# Summits7_Sch.net
KiCad netlist of a schematic drawn in Altium Designer
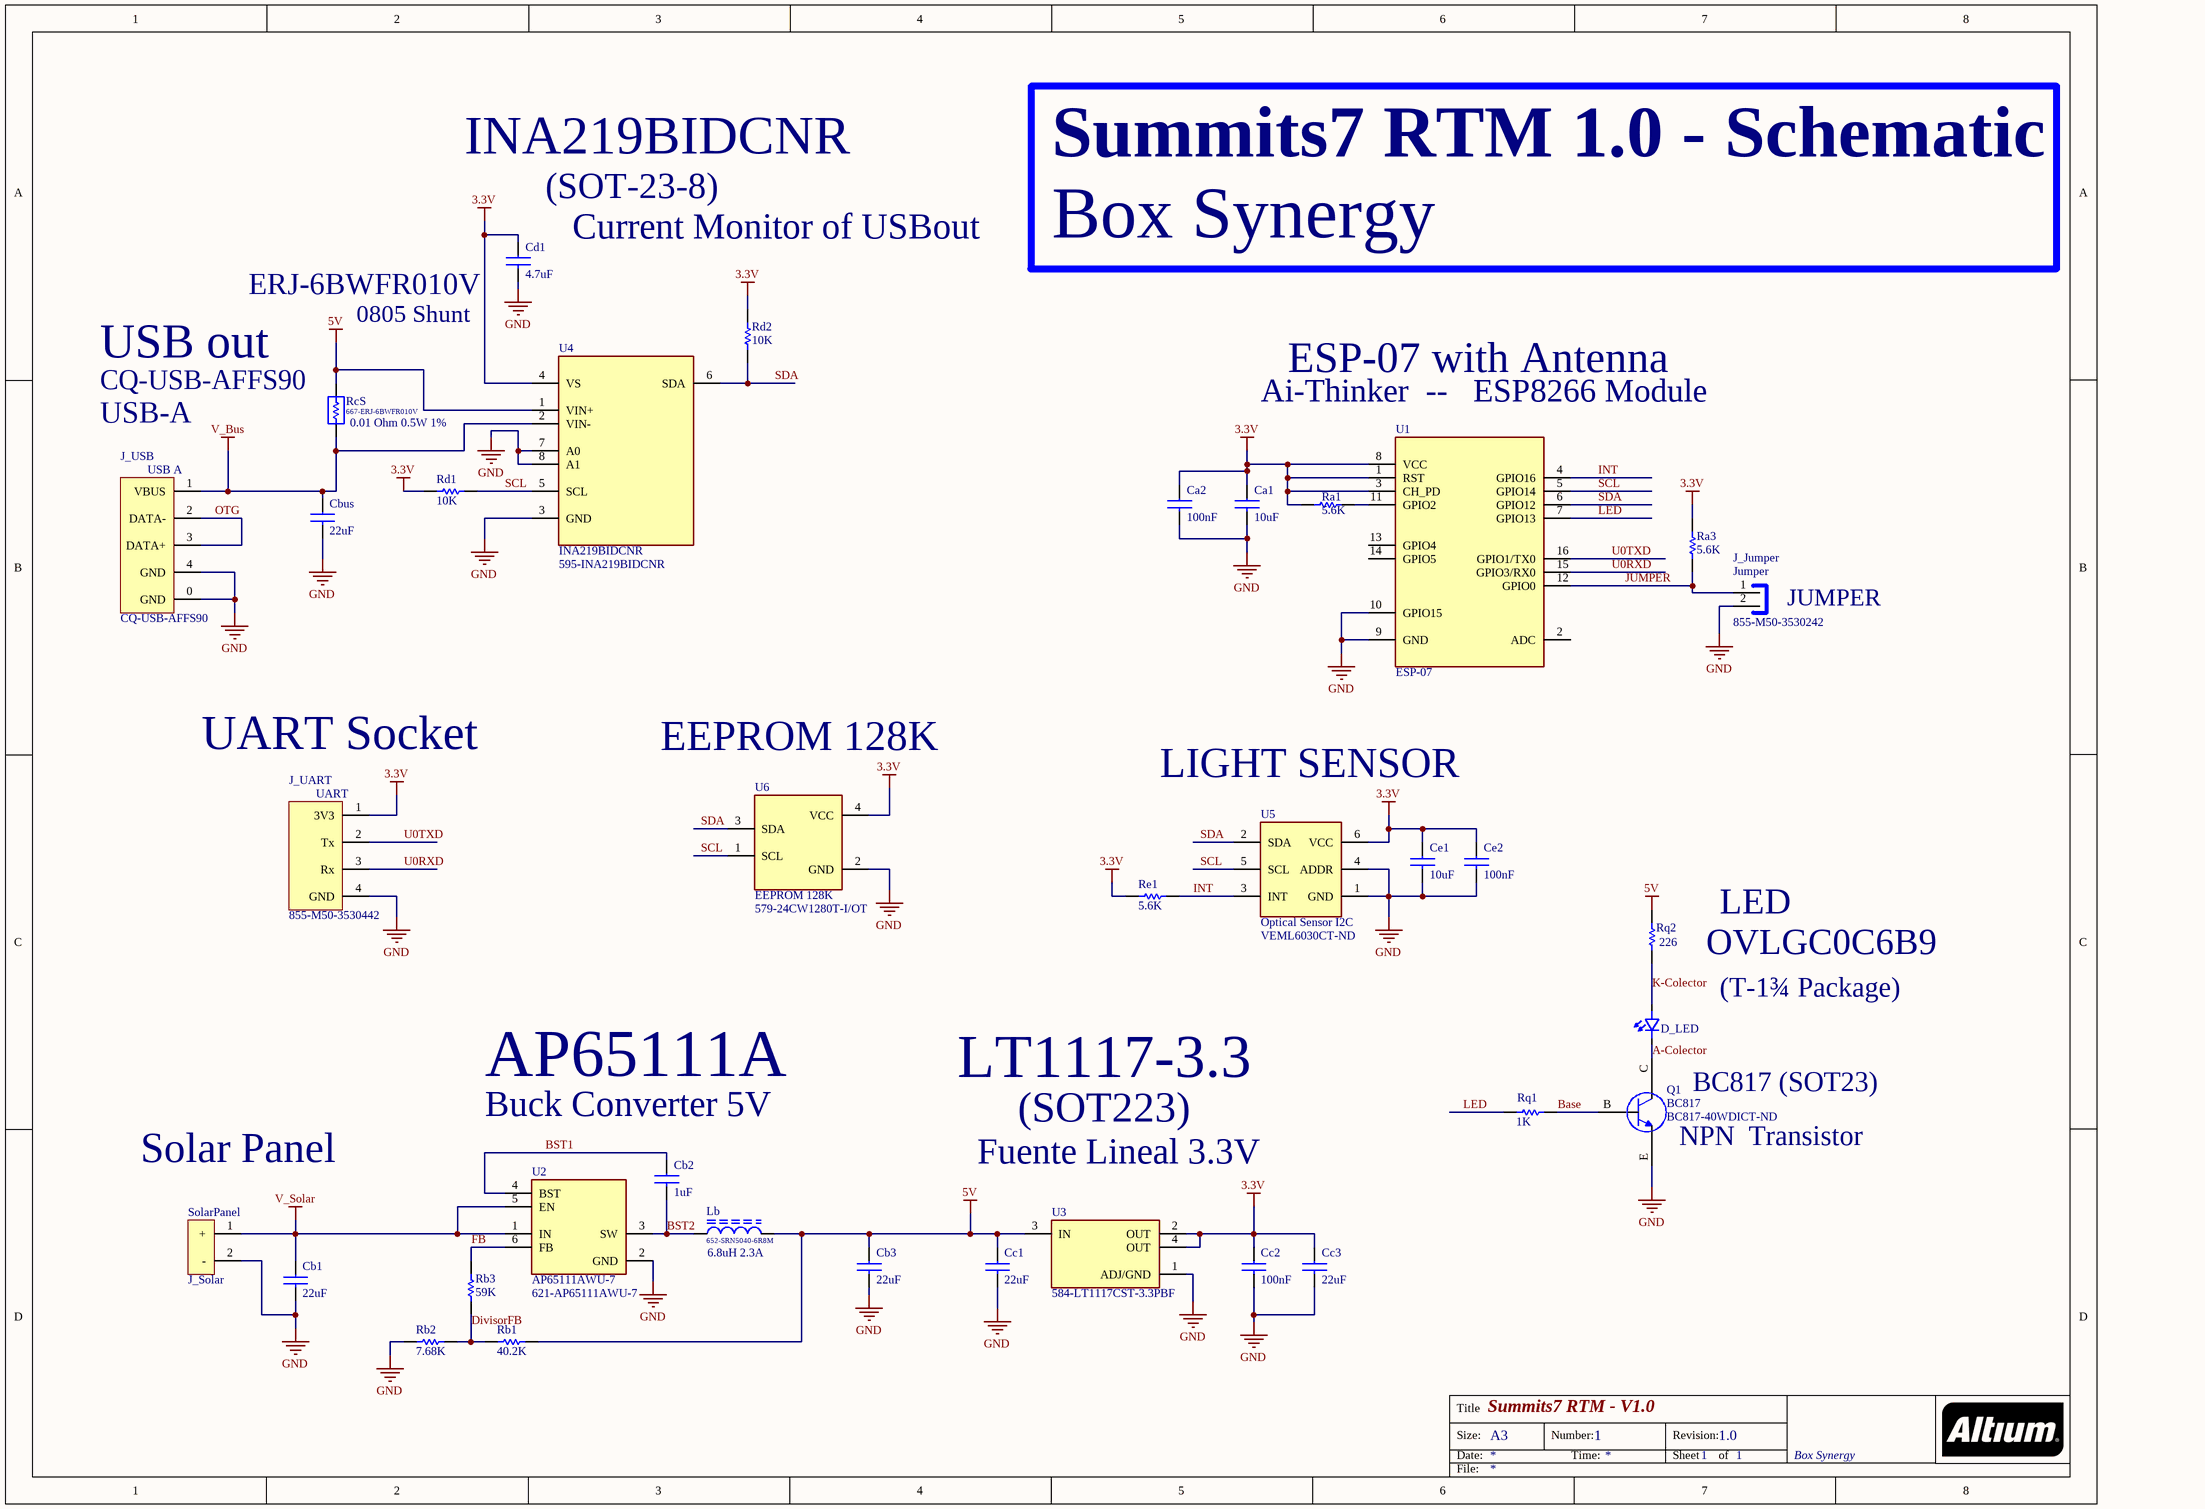
[diagram p0: Summits7_Sch.SchDoc]

(export (version "E")
  (design (tool "Eeschema 10.0.6"))
  (components
    (comp (ref "Ca1")
      (value "10uF")
      (footprint "CAP_0603")
      (description "Capac Ceramic SMD")
      (libsource (lib "Summits7Beta_LIB_Pasivos_Sch") (part "Cap_0603_Ceramic"))
    )
    (comp (ref "Ca2")
      (value "100nF")
      (footprint "CAP_0603")
      (description "Capac Ceramic SMD")
      (libsource (lib "Summits7Beta_LIB_Pasivos_Sch") (part "Cap_0603_Ceramic"))
    )
    (comp (ref "Cb1")
      (value "22uF")
      (footprint "CAP_1210")
      (description "Capac Ceramic SMD")
      (libsource (lib "Summits7Beta_LIB_Pasivos_Sch") (part "Cap_1210_Ceramic"))
    )
    (comp (ref "Cb2")
      (value "1uF")
      (footprint "CAP_0603")
      (description "Capac Ceramic SMD")
      (libsource (lib "Summits7Beta_LIB_Pasivos_Sch") (part "Cap_0603_Ceramic"))
    )
    (comp (ref "Cb3")
      (value "22uF")
      (footprint "CAP_1210")
      (description "Capac Ceramic SMD")
      (libsource (lib "Summits7Beta_LIB_Pasivos_Sch") (part "Cap_1210_Ceramic"))
    )
    (comp (ref "Cbus")
      (value "22uF")
      (footprint "CAP_1210")
      (description "Capac Ceramic SMD")
      (libsource (lib "Summits7Beta_LIB_Pasivos_Sch") (part "Cap_1210_Ceramic"))
    )
    (comp (ref "Cc1")
      (value "22uF")
      (footprint "CAP_0603")
      (description "Capac Ceramic SMD")
      (libsource (lib "Summits7Beta_LIB_Pasivos_Sch") (part "Cap_0603_Ceramic"))
    )
    (comp (ref "Cc2")
      (value "100nF")
      (footprint "CAP_0603")
      (description "Capac Ceramic SMD")
      (libsource (lib "Summits7Beta_LIB_Pasivos_Sch") (part "Cap_0603_Ceramic"))
    )
    (comp (ref "Cc3")
      (value "22uF")
      (footprint "CAP_1210")
      (description "Capac Ceramic SMD")
      (libsource (lib "Summits7Beta_LIB_Pasivos_Sch") (part "Cap_1210_Ceramic"))
    )
    (comp (ref "Cd1")
      (value "4.7uF")
      (footprint "CAP_0603")
      (description "Capac Ceramic SMD")
      (libsource (lib "Summits7Beta_LIB_Pasivos_Sch") (part "Cap_0603_Ceramic"))
    )
    (comp (ref "Ce1")
      (value "10uF")
      (footprint "CAP_0603")
      (description "Capac Ceramic SMD")
      (libsource (lib "Summits7Beta_LIB_Pasivos_Sch") (part "Cap_0603_Ceramic"))
    )
    (comp (ref "Ce2")
      (value "100nF")
      (footprint "CAP_0603")
      (description "Capac Ceramic SMD")
      (libsource (lib "Summits7Beta_LIB_Pasivos_Sch") (part "Cap_0603_Ceramic"))
    )
    (comp (ref "D_LED")
      (value "OVLGC0C6B9")
      (footprint "LED")
      (description "LED Green-Blue 505nm")
      (fields (field (name "MF") "Broadcom Limited") (field (name "MP") "HSMW-C191"))
      (libsource (lib "Summits7Beta_LIB_Otros_Sch") (part "OVLGC0C6B9"))
    )
    (comp (ref "J_Jumper")
      (value "M50-3530242")
      (footprint "JUMPER-1.27 mm")
      (description "1.27mm Pin Header 2x1")
      (fields (field (name "SUPPLIER PART NUMBER 1") "855-M50-3530242"))
      (libsource (lib "Summits7Beta_LIB_Conectores_Sch") (part "Jumper"))
    )
    (comp (ref "J_Solar")
      (value "Connx2_Panel")
      (footprint "PANEL_IN")
      (description "Conector del Panel")
      (libsource (lib "Summits7Beta_LIB_Conectores_Sch") (part "Connx2_Panel"))
    )
    (comp (ref "J_UART")
      (value "M50-3530442")
      (footprint "UART-1.27mm")
      (description "1.27mm Pin Header 4x1")
      (fields (field (name "SUPPLIER PART NUMBER 1") "855-M50-3530442"))
      (libsource (lib "Summits7Beta_LIB_Conectores_Sch") (part "Connx4_UART"))
    )
    (comp (ref "J_USB")
      (value "CQ-USB-AFFS90")
      (footprint "USB-A__IPX8")
      (description "Conector del USB   --   CQ-USB-AFFS90")
      (libsource (lib "Summits7Beta_LIB_Conectores_Sch") (part "USB-A 5V"))
    )
    (comp (ref "Lb")
      (value "6.8uH 2.3A")
      (footprint "Inductor_SRN5040")
      (description "Inductor_SRN5040")
      (fields (field (name "MF") "Vishay Dale") (field (name "SUPPLIER PART NUMBER 1") "652-SRN5040-6R8M"))
      (libsource (lib "Summits7Beta_LIB_Pasivos_Sch") (part "Ind_SRN5040"))
    )
    (comp (ref "Q1")
      (value "BC817")
      (footprint "Transistor_SOT23-3")
      (description "Transistor NPN. Leave 2.5mm height from PCB")
      (fields (field (name "SUPPLIER PART NUMBER 1") "BC817-40WDICT-ND"))
      (libsource (lib "Summits7Beta_LIB_Integrados_Sch") (part "BC817"))
    )
    (comp (ref "Ra1")
      (value "5.6K")
      (footprint "RES_0603")
      (description "Resistor SMD")
      (fields (field (name "PUBLISHER") "Altium Limited"))
      (libsource (lib "Summits7Beta_LIB_Pasivos_Sch") (part "Res_0603"))
    )
    (comp (ref "Ra3")
      (value "5.6K")
      (footprint "RES_0603")
      (description "Resistor SMD")
      (fields (field (name "PUBLISHER") "Altium Limited"))
      (libsource (lib "Summits7Beta_LIB_Pasivos_Sch") (part "Res_0603"))
    )
    (comp (ref "Rb1")
      (value "40.2K")
      (footprint "RES_0603")
      (description "Resistor SMD")
      (fields (field (name "PUBLISHER") "Altium Limited"))
      (libsource (lib "Summits7Beta_LIB_Pasivos_Sch") (part "Res_0603"))
    )
    (comp (ref "Rb2")
      (value "7.68K")
      (footprint "RES_0603")
      (description "Resistor SMD")
      (fields (field (name "PUBLISHER") "Altium Limited"))
      (libsource (lib "Summits7Beta_LIB_Pasivos_Sch") (part "Res_0603"))
    )
    (comp (ref "Rb3")
      (value "59K")
      (footprint "RES_0603")
      (description "Resistor SMD")
      (fields (field (name "PUBLISHER") "Altium Limited"))
      (libsource (lib "Summits7Beta_LIB_Pasivos_Sch") (part "Res_0603"))
    )
    (comp (ref "RcS")
      (value "0.01 Ohm 0.5W 1%")
      (footprint "RES-SHUNT-0805")
      (description "Shunt")
      (fields
        (field (name "SUPPLIER PART NUMBER 1") "667-ERJ-6BWFR010V")
        (field (name "PUBLISHER") "Altium Limited")
      )
      (libsource (lib "Summits7Beta_LIB_Pasivos_Sch") (part "Shunt_0805"))
    )
    (comp (ref "Rd1")
      (value "10K")
      (footprint "RES_0603")
      (description "Resistor SMD")
      (fields (field (name "PUBLISHER") "Altium Limited"))
      (libsource (lib "Summits7Beta_LIB_Pasivos_Sch") (part "Res_0603"))
    )
    (comp (ref "Rd2")
      (value "10K")
      (footprint "RES_0603")
      (description "Resistor SMD")
      (fields (field (name "PUBLISHER") "Altium Limited"))
      (libsource (lib "Summits7Beta_LIB_Pasivos_Sch") (part "Res_0603"))
    )
    (comp (ref "Re1")
      (value "5.6K")
      (footprint "RES_0603")
      (description "Resistor SMD")
      (fields (field (name "PUBLISHER") "Altium Limited"))
      (libsource (lib "Summits7Beta_LIB_Pasivos_Sch") (part "Res_0603"))
    )
    (comp (ref "Rq1")
      (value "1K")
      (footprint "RES_0603")
      (description "Resistor SMD")
      (fields (field (name "PUBLISHER") "Altium Limited"))
      (libsource (lib "Summits7Beta_LIB_Pasivos_Sch") (part "Res_0603"))
    )
    (comp (ref "Rq2")
      (value "226")
      (footprint "RES_0603")
      (description "Resistor SMD")
      (fields (field (name "PUBLISHER") "Altium Limited"))
      (libsource (lib "Summits7Beta_LIB_Pasivos_Sch") (part "Res_0603"))
    )
    (comp (ref "U1")
      (value "ESP-07")
      (footprint "ESP-07")
      (description "ESP07 Module with Antenna Ai-Thinker")
      (fields (field (name "MP") "AP65111AWU-7") (field (name "MF") "Diodes Inc."))
      (libsource (lib "Summits7Beta_LIB_Integrados_Sch") (part "ESP-07"))
    )
    (comp (ref "U2")
      (value "AP65111AWU-7")
      (footprint "AP65111A-SOT23-6")
      (description "Buck Switching Regulator IC Positive Adjustable 0.8V 1 Output 1.5A SOT-23-6 Thin, TSOT-23-6")
      (fields (field (name "MF") "Diodes Inc.") (field (name "SUPPLIER PART NUMBER 1") "621-AP65111AWU-7"))
      (libsource (lib "Summits7Beta_LIB_Integrados_Sch") (part "AP65111AWU-7"))
    )
    (comp (ref "U3")
      (value "LT1117IST-3.3")
      (footprint "LT1117IST-3.3_SOT-223")
      (description "LDO Regulator Pos 3.3V 0.8A Automotive 4-Pin_3+Tab_ SOT-223 Tube")
      (fields
        (field (name "MP") "LT1117IST-5#PBF")
        (field (name "MF") "Analog Devices")
        (field (name "SUPPLIER PART NUMBER 1") "584-LT1117CST-3.3PBF")
      )
      (libsource (lib "Summits7Beta_LIB_Integrados_Sch") (part "LT1117IST-3.3"))
    )
    (comp (ref "U4")
      (value "INA219BIDCNR")
      (footprint "INA219B SOT23")
      (description "Current Monitor Regulator High-Side 10mA SOT-23-8")
      (fields
        (field (name "DIGI-KEY_PART_NUMBER") "296-46420-1-ND")
        (field (name "MF") "Texas Instruments")
        (field (name "SUPPLIER PART NUMBER 1") "595-INA219BIDCNR")
      )
      (libsource (lib "Summits7Beta_LIB_Integrados_Sch") (part "INA219BIDCNR"))
    )
    (comp (ref "U5")
      (value "Optical Sensor I2C")
      (footprint "VEML6030")
      (description "Optical Ambiental Light Sensor I2C with Interrupt")
      (fields (field (name "SUPPLIER PART NUMBER 1") "VEML6030CT-ND"))
      (libsource (lib "Summits7Beta_LIB_Integrados_Sch") (part "VEML6030"))
    )
    (comp (ref "U6")
      (value "EEPROM 128K")
      (footprint "24CW128")
      (fields (field (name "SUPPLIER PART NUMBER 1") "579-24CW1280T-I/OT"))
      (libsource (lib "Summits7Beta_LIB_Integrados_Sch") (part "24CW1280T-I/OT"))
    )
  )
  (nets
    (net (code "1") (name "/A-Colector") (class "Default")
      (node (ref "D_LED") (pin "1") (pinfunction "K_1") (pintype "passive"))
      (node (ref "Q1") (pin "C") (pinfunction "C_C") (pintype "passive"))
    )
    (net (code "2") (name "/BST1") (class "Default")
      (node (ref "Cb2") (pin "1") (pinfunction "1_1") (pintype "passive"))
      (node (ref "U2") (pin "4") (pinfunction "BST_4") (pintype "passive"))
    )
    (net (code "3") (name "/BST2") (class "Default")
      (node (ref "Cb2") (pin "2") (pinfunction "2_2") (pintype "passive"))
      (node (ref "Lb") (pin "2") (pinfunction "2_2") (pintype "passive"))
      (node (ref "U2") (pin "3") (pinfunction "SW_3") (pintype "passive"))
    )
    (net (code "4") (name "/Base") (class "Default")
      (node (ref "Q1") (pin "B") (pinfunction "B_B") (pintype "passive"))
      (node (ref "Rq1") (pin "1") (pinfunction "1_1") (pintype "passive"))
    )
    (net (code "5") (name "/DivisorFB") (class "Default")
      (node (ref "Rb1") (pin "2") (pinfunction "2_2") (pintype "passive"))
      (node (ref "Rb2") (pin "1") (pinfunction "1_1") (pintype "passive"))
      (node (ref "Rb3") (pin "2") (pinfunction "2_2") (pintype "passive"))
    )
    (net (code "6") (name "/FB") (class "Default")
      (node (ref "Rb3") (pin "1") (pinfunction "1_1") (pintype "passive"))
      (node (ref "U2") (pin "6") (pinfunction "FB_6") (pintype "passive"))
    )
    (net (code "7") (name "/INT") (class "Default")
      (node (ref "Re1") (pin "2") (pinfunction "2_2") (pintype "passive"))
      (node (ref "U1") (pin "4") (pinfunction "GPIO16_4") (pintype "passive"))
      (node (ref "U5") (pin "3") (pinfunction "INT_3") (pintype "passive"))
    )
    (net (code "8") (name "/JUMPER") (class "Default")
      (node (ref "J_Jumper") (pin "1") (pinfunction "1_1") (pintype "passive"))
      (node (ref "Ra3") (pin "2") (pinfunction "2_2") (pintype "passive"))
      (node (ref "U1") (pin "12") (pinfunction "GPIO0_12") (pintype "passive"))
    )
    (net (code "9") (name "/K-Colector") (class "Default")
      (node (ref "D_LED") (pin "2") (pinfunction "A_2") (pintype "passive"))
      (node (ref "Rq2") (pin "2") (pinfunction "2_2") (pintype "passive"))
    )
    (net (code "10") (name "/LED") (class "Default")
      (node (ref "Rq1") (pin "2") (pinfunction "2_2") (pintype "passive"))
      (node (ref "U1") (pin "7") (pinfunction "GPIO13_7") (pintype "passive"))
    )
    (net (code "11") (name "/OTG") (class "Default")
      (node (ref "J_USB") (pin "2") (pinfunction "DATA-_2") (pintype "passive"))
      (node (ref "J_USB") (pin "3") (pinfunction "DATA+_3") (pintype "passive"))
    )
    (net (code "12") (name "/SCL") (class "Default")
      (node (ref "Rd1") (pin "2") (pinfunction "2_2") (pintype "passive"))
      (node (ref "U1") (pin "5") (pinfunction "GPIO14_5") (pintype "passive"))
      (node (ref "U4") (pin "5") (pinfunction "SCL_5") (pintype "passive"))
      (node (ref "U5") (pin "5") (pinfunction "SCL_5") (pintype "passive"))
      (node (ref "U6") (pin "1") (pinfunction "SCL_1") (pintype "passive"))
    )
    (net (code "13") (name "/SDA") (class "Default")
      (node (ref "Rd2") (pin "2") (pinfunction "2_2") (pintype "passive"))
      (node (ref "U1") (pin "6") (pinfunction "GPIO12_6") (pintype "passive"))
      (node (ref "U4") (pin "6") (pinfunction "SDA_6") (pintype "passive"))
      (node (ref "U5") (pin "2") (pinfunction "SDA_2") (pintype "passive"))
      (node (ref "U6") (pin "3") (pinfunction "SDA_3") (pintype "passive"))
    )
    (net (code "14") (name "/U0RXD") (class "Default")
      (node (ref "J_UART") (pin "3") (pinfunction "Rx_3") (pintype "passive"))
      (node (ref "U1") (pin "15") (pinfunction "GPIO3/RX0_15") (pintype "passive"))
    )
    (net (code "15") (name "/U0TXD") (class "Default")
      (node (ref "J_UART") (pin "2") (pinfunction "Tx_2") (pintype "passive"))
      (node (ref "U1") (pin "16") (pinfunction "GPIO1/TX0_16") (pintype "passive"))
    )
    (net (code "16") (name "3.3V") (class "Default")
      (node (ref "Ca1") (pin "1") (pinfunction "1_1") (pintype "passive"))
      (node (ref "Ca2") (pin "1") (pinfunction "1_1") (pintype "passive"))
      (node (ref "Cc2") (pin "1") (pinfunction "1_1") (pintype "passive"))
      (node (ref "Cc3") (pin "1") (pinfunction "1_1") (pintype "passive"))
      (node (ref "Cd1") (pin "1") (pinfunction "1_1") (pintype "passive"))
      (node (ref "Ce1") (pin "1") (pinfunction "1_1") (pintype "passive"))
      (node (ref "Ce2") (pin "1") (pinfunction "1_1") (pintype "passive"))
      (node (ref "J_UART") (pin "1") (pinfunction "3V3_1") (pintype "passive"))
      (node (ref "Ra1") (pin "2") (pinfunction "2_2") (pintype "passive"))
      (node (ref "Ra3") (pin "1") (pinfunction "1_1") (pintype "passive"))
      (node (ref "Rd1") (pin "1") (pinfunction "1_1") (pintype "passive"))
      (node (ref "Rd2") (pin "1") (pinfunction "1_1") (pintype "passive"))
      (node (ref "Re1") (pin "1") (pinfunction "1_1") (pintype "passive"))
      (node (ref "U1") (pin "1") (pinfunction "RST_1") (pintype "passive"))
      (node (ref "U1") (pin "3") (pinfunction "CH_PD_3") (pintype "passive"))
      (node (ref "U1") (pin "8") (pinfunction "VCC_8") (pintype "passive"))
      (node (ref "U3") (pin "2") (pinfunction "OUT_2") (pintype "passive"))
      (node (ref "U3") (pin "4") (pinfunction "OUT_4") (pintype "passive"))
      (node (ref "U4") (pin "4") (pinfunction "VS_4") (pintype "power_in"))
      (node (ref "U5") (pin "6") (pinfunction "VCC_6") (pintype "passive"))
      (node (ref "U6") (pin "4") (pinfunction "VCC_4") (pintype "passive"))
    )
    (net (code "17") (name "5V") (class "Default")
      (node (ref "Cb3") (pin "1") (pinfunction "1_1") (pintype "passive"))
      (node (ref "Cc1") (pin "1") (pinfunction "1_1") (pintype "passive"))
      (node (ref "Lb") (pin "1") (pinfunction "1_1") (pintype "passive"))
      (node (ref "Rb1") (pin "1") (pinfunction "1_1") (pintype "passive"))
      (node (ref "RcS") (pin "1") (pinfunction "1_1") (pintype "passive"))
      (node (ref "Rq2") (pin "1") (pinfunction "1_1") (pintype "passive"))
      (node (ref "U3") (pin "3") (pinfunction "IN_3") (pintype "passive"))
      (node (ref "U4") (pin "1") (pinfunction "VIN+_1") (pintype "passive"))
    )
    (net (code "18") (name "GND") (class "Default")
      (node (ref "Ca1") (pin "2") (pinfunction "2_2") (pintype "passive"))
      (node (ref "Ca2") (pin "2") (pinfunction "2_2") (pintype "passive"))
      (node (ref "Cb1") (pin "2") (pinfunction "2_2") (pintype "passive"))
      (node (ref "Cb3") (pin "2") (pinfunction "2_2") (pintype "passive"))
      (node (ref "Cbus") (pin "2") (pinfunction "2_2") (pintype "passive"))
      (node (ref "Cc1") (pin "2") (pinfunction "2_2") (pintype "passive"))
      (node (ref "Cc2") (pin "2") (pinfunction "2_2") (pintype "passive"))
      (node (ref "Cc3") (pin "2") (pinfunction "2_2") (pintype "passive"))
      (node (ref "Cd1") (pin "2") (pinfunction "2_2") (pintype "passive"))
      (node (ref "Ce1") (pin "2") (pinfunction "2_2") (pintype "passive"))
      (node (ref "Ce2") (pin "2") (pinfunction "2_2") (pintype "passive"))
      (node (ref "J_Jumper") (pin "2") (pinfunction "2_2") (pintype "passive"))
      (node (ref "J_Solar") (pin "2") (pinfunction "-_2") (pintype "passive"))
      (node (ref "J_UART") (pin "4") (pinfunction "GND_4") (pintype "passive"))
      (node (ref "J_USB") (pin "0") (pinfunction "GND_0") (pintype "passive"))
      (node (ref "J_USB") (pin "4") (pinfunction "GND_4") (pintype "passive"))
      (node (ref "Q1") (pin "E") (pinfunction "E_E") (pintype "passive"))
      (node (ref "Rb2") (pin "2") (pinfunction "2_2") (pintype "passive"))
      (node (ref "U1") (pin "10") (pinfunction "GPIO15_10") (pintype "passive"))
      (node (ref "U1") (pin "9") (pinfunction "GND_9") (pintype "passive"))
      (node (ref "U2") (pin "2") (pinfunction "GND_2") (pintype "passive"))
      (node (ref "U3") (pin "1") (pinfunction "ADJ/GND_1") (pintype "passive"))
      (node (ref "U4") (pin "3") (pinfunction "GND_3") (pintype "passive"))
      (node (ref "U4") (pin "7") (pinfunction "A0_7") (pintype "passive"))
      (node (ref "U4") (pin "8") (pinfunction "A1_8") (pintype "passive"))
      (node (ref "U5") (pin "1") (pinfunction "GND_1") (pintype "passive"))
      (node (ref "U5") (pin "4") (pinfunction "ADDR_4") (pintype "passive"))
      (node (ref "U6") (pin "2") (pinfunction "GND_2") (pintype "passive"))
    )
    (net (code "19") (name "Net-(U1-GPIO2)") (class "Default")
      (node (ref "Ra1") (pin "1") (pinfunction "1_1") (pintype "passive"))
      (node (ref "U1") (pin "11") (pinfunction "GPIO2_11") (pintype "passive"))
    )
    (net (code "20") (name "V_Bus") (class "Default")
      (node (ref "Cbus") (pin "1") (pinfunction "1_1") (pintype "passive"))
      (node (ref "J_USB") (pin "1") (pinfunction "VBUS_1") (pintype "power_in"))
      (node (ref "RcS") (pin "2") (pinfunction "2_2") (pintype "passive"))
      (node (ref "U4") (pin "2") (pinfunction "VIN-_2") (pintype "passive"))
    )
    (net (code "21") (name "V_Solar") (class "Default")
      (node (ref "Cb1") (pin "1") (pinfunction "1_1") (pintype "passive"))
      (node (ref "J_Solar") (pin "1") (pinfunction "+_1") (pintype "passive"))
      (node (ref "U2") (pin "1") (pinfunction "IN_1") (pintype "passive"))
      (node (ref "U2") (pin "5") (pinfunction "EN_5") (pintype "passive"))
    )
    (net (code "22") (name "unconnected-(U1-ADC-Pad2)") (class "Default")
      (node (ref "U1") (pin "2") (pinfunction "ADC_2") (pintype "passive"))
    )
    (net (code "23") (name "unconnected-(U1-GPIO4-Pad13)") (class "Default")
      (node (ref "U1") (pin "13") (pinfunction "GPIO4_13") (pintype "passive"))
    )
    (net (code "24") (name "unconnected-(U1-GPIO5-Pad14)") (class "Default")
      (node (ref "U1") (pin "14") (pinfunction "GPIO5_14") (pintype "passive"))
    )
  )
)
